# DCmotorBreadBoard.net
KiCad netlist of a schematic drawn in EAGLE
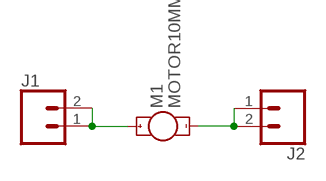
[diagram p0: schematic, sheet 1]

(export (version "E")
  (design (tool "Eeschema 10.0.6"))
  (components
    (comp (ref "J1")
      (value "CONN_02")
      (footprint "eagle-import:1X02")
      (libsource (lib "eagle-import") (part "CONN_02"))
    )
    (comp (ref "J2")
      (value "CONN_02")
      (footprint "eagle-import:1X02")
      (libsource (lib "eagle-import") (part "CONN_02"))
    )
    (comp (ref "M1")
      (value "MOTOR10MM")
      (footprint "eagle-import:VIBE-MOTOR-10MM")
      (libsource (lib "eagle-import") (part "MOTOR10MM"))
    )
  )
  (nets
    (net (code "1") (name "Net-(J1-Pad1)") (class "Default")
      (node (ref "J1") (pin "1") (pinfunction "1_1") (pintype "passive"))
      (node (ref "J1") (pin "2") (pinfunction "2_2") (pintype "passive"))
      (node (ref "M1") (pin "+") (pinfunction "+_+") (pintype "bidirectional"))
    )
    (net (code "2") (name "Net-(J2-Pad1)") (class "Default")
      (node (ref "J2") (pin "1") (pinfunction "1_1") (pintype "passive"))
      (node (ref "J2") (pin "2") (pinfunction "2_2") (pintype "passive"))
      (node (ref "M1") (pin "-") (pinfunction "-_-") (pintype "bidirectional"))
    )
  )
)
